# MainBoard_V100_PSU_DIG.net
KiCad netlist of a schematic drawn in Altium Designer
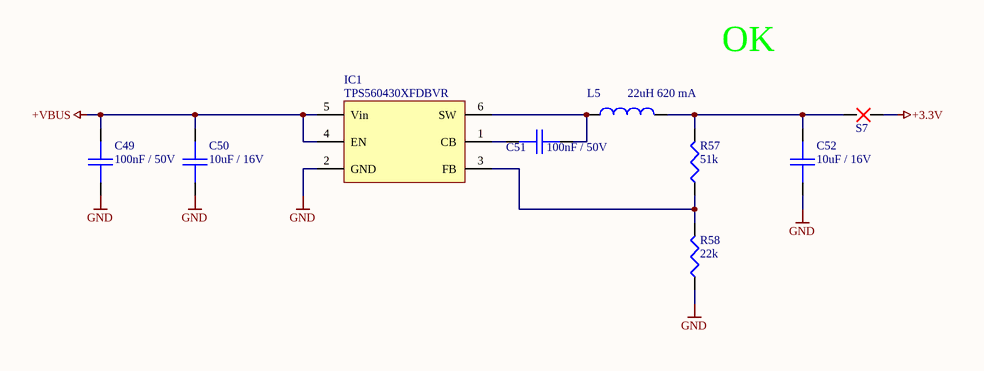
[diagram p0: MainBoard_V100_PSU_DIG.SchDoc]

(export (version "E")
  (design (tool "Eeschema 10.0.6"))
  (components
    (comp (ref "C49")
      (value "100nF / 50V")
      (footprint "0805_C")
      (description "100nF 50V X7R")
      (fields (field (name "PART NUMBER") "SMD0805-100nF-50V"))
      (libsource (lib "ALTIUM_DB_LIB") (part "CAP_NONPOL"))
    )
    (comp (ref "C50")
      (value "10uF / 16V")
      (footprint "0805_C")
      (description "10uF 16V X5R")
      (fields (field (name "PART NUMBER") "SMD0805-10uF-16V"))
      (libsource (lib "ALTIUM_DB_LIB") (part "CAP_NONPOL"))
    )
    (comp (ref "C51")
      (value "100nF / 50V")
      (footprint "0805_C")
      (description "100nF 50V X7R")
      (fields (field (name "PART NUMBER") "SMD0805-100nF-50V"))
      (libsource (lib "ALTIUM_DB_LIB") (part "CAP_NONPOL"))
    )
    (comp (ref "C52")
      (value "10uF / 16V")
      (footprint "0805_C")
      (description "10uF 16V X5R")
      (fields (field (name "PART NUMBER") "SMD0805-10uF-16V"))
      (libsource (lib "ALTIUM_DB_LIB") (part "CAP_NONPOL"))
    )
    (comp (ref "IC1")
      (value "TPS560430XFDBVR")
      (footprint "SOT-23-6")
      (description "SIMPLE SWITCHER 4-V to 36-V, 600-mA Synchronous Step-Down Converter")
      (libsource (lib "ALTIUM_DB_LIB") (part "TPS560430"))
    )
    (comp (ref "L5")
      (value "22uH 620 mA")
      (footprint "1210")
      (description "22uH 620 mA 1210")
      (fields (field (name "PART NUMBER") "CBC3225T220KR"))
      (libsource (lib "ALTIUM_DB_LIB") (part "INDUCTOR"))
    )
    (comp (ref "R57")
      (value "51k")
      (footprint "0805")
      (description "51k 0805 0.125W 5%")
      (fields (field (name "PART NUMBER") "SMD0805-51k 5%"))
      (libsource (lib "ALTIUM_DB_LIB") (part "RESISTOR"))
    )
    (comp (ref "R58")
      (value "22k")
      (footprint "0805")
      (description "22k 0805 0.1W 5%")
      (fields (field (name "PART NUMBER") "SMD0805-22k-5%"))
      (libsource (lib "ALTIUM_DB_LIB") (part "RESISTOR"))
    )
    (comp (ref "S7")
      (value "SPLITER")
      (footprint "SPLITER2_30mil_9mil")
      (description "SPLITER2_30mil_9mil")
      (libsource (lib "ALTIUM_DB_LIB") (part "SPLITER"))
    )
  )
  (nets
    (net (code "1") (name "+3.3V") (class "Default")
      (node (ref "S7") (pin "2") (pinfunction "2_2") (pintype "passive"))
    )
    (net (code "2") (name "+VBUS") (class "Default")
      (node (ref "C49") (pin "1") (pintype "passive"))
      (node (ref "C50") (pin "1") (pintype "passive"))
      (node (ref "IC1") (pin "4") (pinfunction "EN_4") (pintype "passive"))
      (node (ref "IC1") (pin "5") (pinfunction "Vin_5") (pintype "passive"))
    )
    (net (code "3") (name "GND") (class "Default")
      (node (ref "C49") (pin "2") (pintype "passive"))
      (node (ref "C50") (pin "2") (pintype "passive"))
      (node (ref "C52") (pin "2") (pintype "passive"))
      (node (ref "IC1") (pin "2") (pinfunction "GND_2") (pintype "passive"))
      (node (ref "R58") (pin "1") (pintype "passive"))
    )
    (net (code "4") (name "Net-(C52-Pad1)") (class "Default")
      (node (ref "C52") (pin "1") (pintype "passive"))
      (node (ref "L5") (pin "2") (pinfunction "2_2") (pintype "passive"))
      (node (ref "R57") (pin "2") (pintype "passive"))
      (node (ref "S7") (pin "1") (pinfunction "1_1") (pintype "passive"))
    )
    (net (code "5") (name "Net-(IC1-CB)") (class "Default")
      (node (ref "C51") (pin "1") (pintype "passive"))
      (node (ref "IC1") (pin "1") (pinfunction "CB_1") (pintype "passive"))
    )
    (net (code "6") (name "Net-(IC1-FB)") (class "Default")
      (node (ref "IC1") (pin "3") (pinfunction "FB_3") (pintype "passive"))
      (node (ref "R57") (pin "1") (pintype "passive"))
      (node (ref "R58") (pin "2") (pintype "passive"))
    )
    (net (code "7") (name "Net-(IC1-SW)") (class "Default")
      (node (ref "C51") (pin "2") (pintype "passive"))
      (node (ref "IC1") (pin "6") (pinfunction "SW_6") (pintype "passive"))
      (node (ref "L5") (pin "1") (pinfunction "1_1") (pintype "passive"))
    )
  )
)
